# leddriver.net
KiCad netlist of a schematic drawn in EAGLE
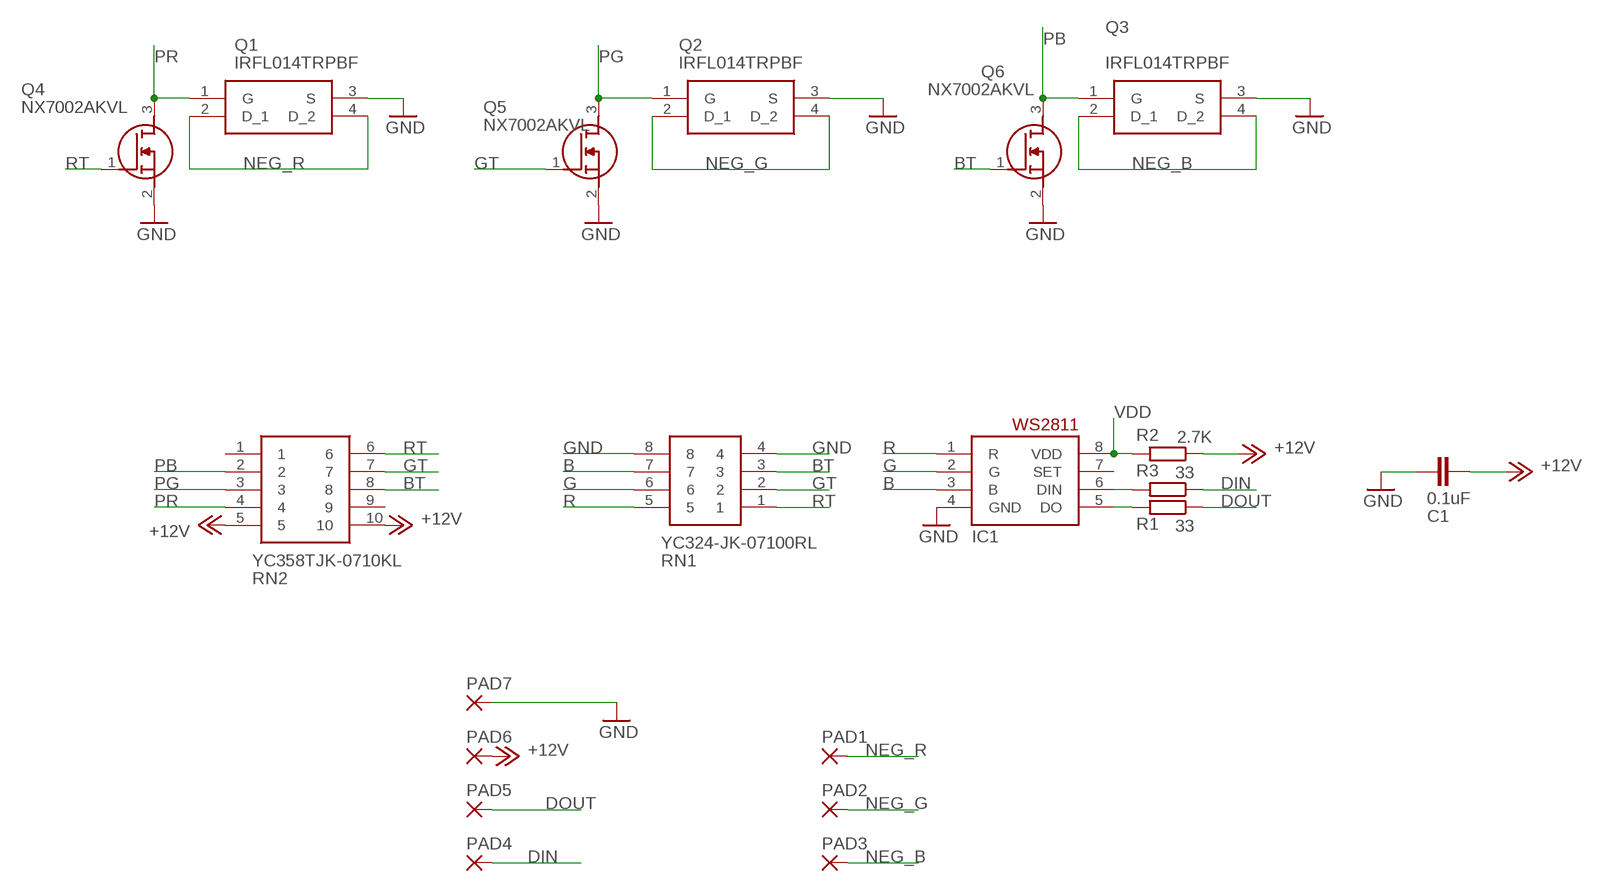
[diagram p0: schematic, sheet 1]

(export (version "E")
  (design (tool "Eeschema 10.0.6"))
  (components
    (comp (ref "C1")
      (value "0.1uF")
      (footprint "eagle-import:C1206")
      (libsource (lib "eagle-import") (part "C-EUC1206"))
    )
    (comp (ref "IC1")
      (value "WS2811-SOP8")
      (footprint "eagle-import:SO08-SKINNYPADS")
      (libsource (lib "eagle-import") (part "WS2811-SOP8"))
    )
    (comp (ref "PAD1")
      (value "3,81/1,4")
      (footprint "eagle-import:3,81_1,4")
      (libsource (lib "eagle-import") (part "3,81/1,4"))
    )
    (comp (ref "PAD2")
      (value "3,81/1,4")
      (footprint "eagle-import:3,81_1,4")
      (libsource (lib "eagle-import") (part "3,81/1,4"))
    )
    (comp (ref "PAD3")
      (value "3,81/1,4")
      (footprint "eagle-import:3,81_1,4")
      (libsource (lib "eagle-import") (part "3,81/1,4"))
    )
    (comp (ref "PAD4")
      (value "3,81/1,4")
      (footprint "eagle-import:3,81_1,4")
      (libsource (lib "eagle-import") (part "3,81/1,4"))
    )
    (comp (ref "PAD5")
      (value "3,81/1,4")
      (footprint "eagle-import:3,81_1,4")
      (libsource (lib "eagle-import") (part "3,81/1,4"))
    )
    (comp (ref "PAD6")
      (value "3,81/1,4")
      (footprint "eagle-import:3,81_1,4")
      (libsource (lib "eagle-import") (part "3,81/1,4"))
    )
    (comp (ref "PAD7")
      (value "3,81/1,4")
      (footprint "eagle-import:3,81_1,4")
      (libsource (lib "eagle-import") (part "3,81/1,4"))
    )
    (comp (ref "Q1")
      (value "IRFL014TRPBF")
      (footprint "eagle-import:SOT230P700X180-4N")
      (fields (field (name "MOUSER_PART_NUMBER") "844-IRFL014TRPBF"))
      (libsource (lib "eagle-import") (part "IRFL014TRPBF"))
    )
    (comp (ref "Q2")
      (value "IRFL014TRPBF")
      (footprint "eagle-import:SOT230P700X180-4N")
      (fields (field (name "MOUSER_PART_NUMBER") "844-IRFL014TRPBF"))
      (libsource (lib "eagle-import") (part "IRFL014TRPBF"))
    )
    (comp (ref "Q3")
      (value "IRFL014TRPBF")
      (footprint "eagle-import:SOT230P700X180-4N")
      (fields (field (name "MOUSER_PART_NUMBER") "844-IRFL014TRPBF"))
      (libsource (lib "eagle-import") (part "IRFL014TRPBF"))
    )
    (comp (ref "Q4")
      (value "NX7002AKVL")
      (footprint "eagle-import:SOT95P230X110-3N")
      (fields (field (name "MOUSER_PART_NUMBER") "771-NX7002AKVL"))
      (libsource (lib "eagle-import") (part "NX7002AKVL"))
    )
    (comp (ref "Q5")
      (value "NX7002AKVL")
      (footprint "eagle-import:SOT95P230X110-3N")
      (fields (field (name "MOUSER_PART_NUMBER") "771-NX7002AKVL"))
      (libsource (lib "eagle-import") (part "NX7002AKVL"))
    )
    (comp (ref "Q6")
      (value "NX7002AKVL")
      (footprint "eagle-import:SOT95P230X110-3N")
      (fields (field (name "MOUSER_PART_NUMBER") "771-NX7002AKVL"))
      (libsource (lib "eagle-import") (part "NX7002AKVL"))
    )
    (comp (ref "R1")
      (value "33")
      (footprint "eagle-import:R1206")
      (libsource (lib "eagle-import") (part "R-EU_R1206"))
    )
    (comp (ref "R2")
      (value "2.7K")
      (footprint "eagle-import:R1206")
      (libsource (lib "eagle-import") (part "R-EU_R1206"))
    )
    (comp (ref "R3")
      (value "33")
      (footprint "eagle-import:R1206")
      (libsource (lib "eagle-import") (part "R-EU_R1206"))
    )
    (comp (ref "RN1")
      (value "YC324-JK-07100RL")
      (footprint "eagle-import:YC324JK07100RL")
      (fields (field (name "MOUSER_PART_NUMBER") "603-YC324-JK-07100RL"))
      (libsource (lib "eagle-import") (part "YC324-JK-07100RL"))
    )
    (comp (ref "RN2")
      (value "YC358TJK-0710KL")
      (footprint "eagle-import:YC358T")
      (fields (field (name "MOUSER_PART_NUMBER") "603-YC358TJK-0710KL"))
      (libsource (lib "eagle-import") (part "YC358TJK-0710KL"))
    )
  )
  (nets
    (net (code "1") (name "+12V") (class "Default")
      (node (ref "C1") (pin "2") (pinfunction "2_2") (pintype "passive"))
      (node (ref "PAD6") (pin "1") (pinfunction "P_1") (pintype "passive"))
      (node (ref "R2") (pin "1") (pinfunction "1_1") (pintype "passive"))
      (node (ref "RN2") (pin "10") (pinfunction "10_10") (pintype "bidirectional"))
      (node (ref "RN2") (pin "5") (pinfunction "5_5") (pintype "bidirectional"))
    )
    (net (code "2") (name "/B") (class "Default")
      (node (ref "IC1") (pin "3") (pinfunction "B_3") (pintype "open_collector"))
      (node (ref "RN1") (pin "7") (pinfunction "7_7") (pintype "bidirectional"))
    )
    (net (code "3") (name "/BT") (class "Default")
      (node (ref "Q6") (pin "1") (pinfunction "G_1") (pintype "bidirectional"))
      (node (ref "RN1") (pin "3") (pinfunction "3_3") (pintype "bidirectional"))
      (node (ref "RN2") (pin "8") (pinfunction "8_8") (pintype "bidirectional"))
    )
    (net (code "4") (name "/DIN") (class "Default")
      (node (ref "PAD4") (pin "1") (pinfunction "P_1") (pintype "passive"))
      (node (ref "R3") (pin "1") (pinfunction "1_1") (pintype "passive"))
    )
    (net (code "5") (name "/DOUT") (class "Default")
      (node (ref "PAD5") (pin "1") (pinfunction "P_1") (pintype "passive"))
      (node (ref "R1") (pin "1") (pinfunction "1_1") (pintype "passive"))
    )
    (net (code "6") (name "/G") (class "Default")
      (node (ref "IC1") (pin "2") (pinfunction "G_2") (pintype "open_collector"))
      (node (ref "RN1") (pin "6") (pinfunction "6_6") (pintype "bidirectional"))
    )
    (net (code "7") (name "/GT") (class "Default")
      (node (ref "Q5") (pin "1") (pinfunction "G_1") (pintype "bidirectional"))
      (node (ref "RN1") (pin "2") (pinfunction "2_2") (pintype "bidirectional"))
      (node (ref "RN2") (pin "7") (pinfunction "7_7") (pintype "bidirectional"))
    )
    (net (code "8") (name "/NEG_B") (class "Default")
      (node (ref "PAD3") (pin "1") (pinfunction "P_1") (pintype "passive"))
      (node (ref "Q3") (pin "2") (pinfunction "D_1_2") (pintype "bidirectional"))
      (node (ref "Q3") (pin "4") (pinfunction "D_2_4") (pintype "bidirectional"))
    )
    (net (code "9") (name "/NEG_G") (class "Default")
      (node (ref "PAD2") (pin "1") (pinfunction "P_1") (pintype "passive"))
      (node (ref "Q2") (pin "2") (pinfunction "D_1_2") (pintype "bidirectional"))
      (node (ref "Q2") (pin "4") (pinfunction "D_2_4") (pintype "bidirectional"))
    )
    (net (code "10") (name "/NEG_R") (class "Default")
      (node (ref "PAD1") (pin "1") (pinfunction "P_1") (pintype "passive"))
      (node (ref "Q1") (pin "2") (pinfunction "D_1_2") (pintype "bidirectional"))
      (node (ref "Q1") (pin "4") (pinfunction "D_2_4") (pintype "bidirectional"))
    )
    (net (code "11") (name "/PB") (class "Default")
      (node (ref "Q3") (pin "1") (pinfunction "G_1") (pintype "bidirectional"))
      (node (ref "Q6") (pin "3") (pinfunction "D_3") (pintype "bidirectional"))
      (node (ref "RN2") (pin "2") (pinfunction "2_2") (pintype "bidirectional"))
    )
    (net (code "12") (name "/PG") (class "Default")
      (node (ref "Q2") (pin "1") (pinfunction "G_1") (pintype "bidirectional"))
      (node (ref "Q5") (pin "3") (pinfunction "D_3") (pintype "bidirectional"))
      (node (ref "RN2") (pin "3") (pinfunction "3_3") (pintype "bidirectional"))
    )
    (net (code "13") (name "/PR") (class "Default")
      (node (ref "Q1") (pin "1") (pinfunction "G_1") (pintype "bidirectional"))
      (node (ref "Q4") (pin "3") (pinfunction "D_3") (pintype "bidirectional"))
      (node (ref "RN2") (pin "4") (pinfunction "4_4") (pintype "bidirectional"))
    )
    (net (code "14") (name "/R") (class "Default")
      (node (ref "IC1") (pin "1") (pinfunction "R_1") (pintype "open_collector"))
      (node (ref "RN1") (pin "5") (pinfunction "5_5") (pintype "bidirectional"))
    )
    (net (code "15") (name "/RT") (class "Default")
      (node (ref "Q4") (pin "1") (pinfunction "G_1") (pintype "bidirectional"))
      (node (ref "RN1") (pin "1") (pinfunction "1_1") (pintype "bidirectional"))
      (node (ref "RN2") (pin "6") (pinfunction "6_6") (pintype "bidirectional"))
    )
    (net (code "16") (name "/VDD") (class "Default")
      (node (ref "IC1") (pin "8") (pinfunction "VDD_8") (pintype "power_in"))
      (node (ref "R2") (pin "2") (pinfunction "2_2") (pintype "passive"))
    )
    (net (code "17") (name "GND") (class "Default")
      (node (ref "C1") (pin "1") (pinfunction "1_1") (pintype "passive"))
      (node (ref "IC1") (pin "4") (pinfunction "GND_4") (pintype "power_in"))
      (node (ref "PAD7") (pin "1") (pinfunction "P_1") (pintype "passive"))
      (node (ref "Q1") (pin "3") (pinfunction "S_3") (pintype "bidirectional"))
      (node (ref "Q2") (pin "3") (pinfunction "S_3") (pintype "bidirectional"))
      (node (ref "Q3") (pin "3") (pinfunction "S_3") (pintype "bidirectional"))
      (node (ref "Q4") (pin "2") (pinfunction "S_2") (pintype "bidirectional"))
      (node (ref "Q5") (pin "2") (pinfunction "S_2") (pintype "bidirectional"))
      (node (ref "Q6") (pin "2") (pinfunction "S_2") (pintype "bidirectional"))
      (node (ref "RN1") (pin "4") (pinfunction "4_4") (pintype "bidirectional"))
      (node (ref "RN1") (pin "8") (pinfunction "8_8") (pintype "bidirectional"))
    )
    (net (code "18") (name "Net-(IC1-DIN)") (class "Default")
      (node (ref "IC1") (pin "6") (pinfunction "DIN_6") (pintype "input"))
      (node (ref "R3") (pin "2") (pinfunction "2_2") (pintype "passive"))
    )
    (net (code "19") (name "Net-(IC1-DO)") (class "Default")
      (node (ref "IC1") (pin "5") (pinfunction "DO_5") (pintype "output"))
      (node (ref "R1") (pin "2") (pinfunction "2_2") (pintype "passive"))
    )
    (net (code "20") (name "unconnected-(IC1-SET-Pad7)") (class "Default")
      (node (ref "IC1") (pin "7") (pinfunction "SET_7") (pintype "input"))
    )
    (net (code "21") (name "unconnected-(RN2-Pad1)") (class "Default")
      (node (ref "RN2") (pin "1") (pinfunction "1_1") (pintype "bidirectional"))
    )
    (net (code "22") (name "unconnected-(RN2-Pad9)") (class "Default")
      (node (ref "RN2") (pin "9") (pinfunction "9_9") (pintype "bidirectional"))
    )
  )
)
